# tick-mk-5_0_0.net
KiCad netlist of a schematic drawn in EAGLE
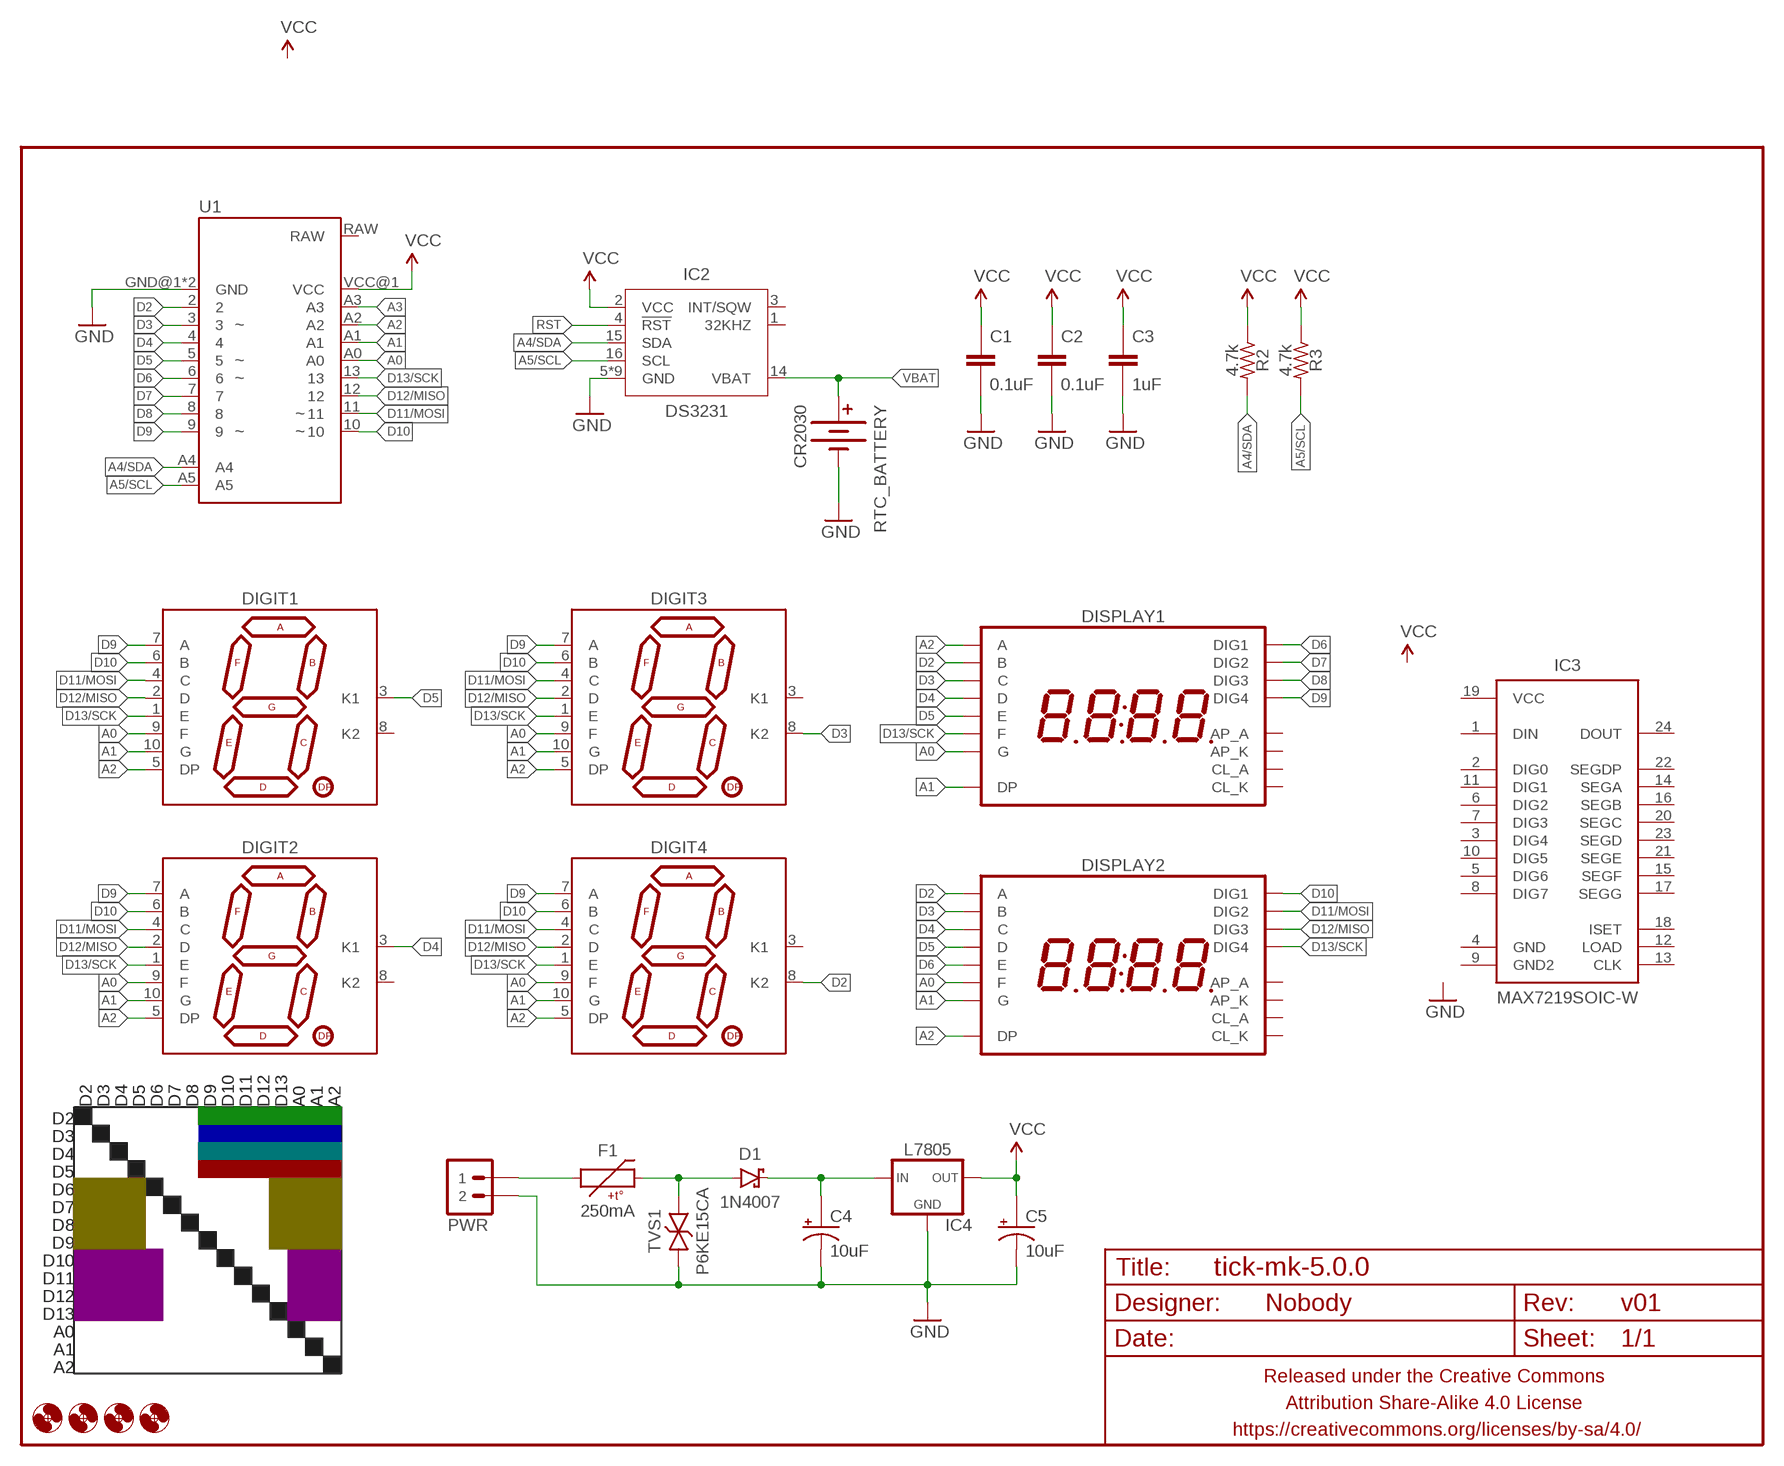
[diagram p0: schematic, sheet 1]

(export (version "E")
  (design (tool "Eeschema 10.0.6"))
  (components
    (comp (ref "C1")
      (value "0.1uF")
      (footprint "eagle-import:C025-024X044")
      (libsource (lib "eagle-import") (part "CAPACITOR-CERAMIC025-024X044"))
    )
    (comp (ref "C2")
      (value "0.1uF")
      (footprint "eagle-import:C025-024X044")
      (libsource (lib "eagle-import") (part "CAPACITOR-CERAMIC025-024X044"))
    )
    (comp (ref "C3")
      (value "1uF")
      (footprint "eagle-import:C025-024X044")
      (libsource (lib "eagle-import") (part "CAPACITOR-CERAMIC025-024X044"))
    )
    (comp (ref "C4")
      (value "10uF")
      (footprint "eagle-import:E2-5")
      (libsource (lib "eagle-import") (part "CAPACITOR-POLARIZEDE2-5"))
    )
    (comp (ref "C5")
      (value "10uF")
      (footprint "eagle-import:E2-5")
      (libsource (lib "eagle-import") (part "CAPACITOR-POLARIZEDE2-5"))
    )
    (comp (ref "D1")
      (value "1N4007")
      (footprint "eagle-import:DIODE-10.16MM")
      (libsource (lib "eagle-import") (part "DIODE-SCHOTTKYPTH-10.16MM"))
    )
    (comp (ref "DIGIT1")
      (value "7SEG_1DIGPTH-25.4MM-BARE")
      (footprint "eagle-import:7SEG_1DIG_25.4MM_NOSILK")
      (libsource (lib "eagle-import") (part "7SEG_1DIGPTH-25.4MM-BARE"))
    )
    (comp (ref "DIGIT2")
      (value "7SEG_1DIGPTH-25.4MM-BARE")
      (footprint "eagle-import:7SEG_1DIG_25.4MM_NOSILK")
      (libsource (lib "eagle-import") (part "7SEG_1DIGPTH-25.4MM-BARE"))
    )
    (comp (ref "DIGIT3")
      (value "7SEG_1DIGPTH-25.4MM-BARE")
      (footprint "eagle-import:7SEG_1DIG_25.4MM_NOSILK")
      (libsource (lib "eagle-import") (part "7SEG_1DIGPTH-25.4MM-BARE"))
    )
    (comp (ref "DIGIT4")
      (value "7SEG_1DIGPTH-25.4MM-BARE")
      (footprint "eagle-import:7SEG_1DIG_25.4MM_NOSILK")
      (libsource (lib "eagle-import") (part "7SEG_1DIGPTH-25.4MM-BARE"))
    )
    (comp (ref "DISPLAY1")
      (value "7SEG_4DIGIT_COLON_APOS")
      (footprint "eagle-import:7SEG_4DIG_10MM")
      (libsource (lib "eagle-import") (part "7SEG_4DIGIT_COLON_APOS"))
    )
    (comp (ref "DISPLAY2")
      (value "7SEG_4DIGIT_COLON_APOS")
      (footprint "eagle-import:7SEG_4DIG_10MM")
      (libsource (lib "eagle-import") (part "7SEG_4DIGIT_COLON_APOS"))
    )
    (comp (ref "F1")
      (value "250mA")
      (footprint "eagle-import:PTC-PTH-5.08MM")
      (libsource (lib "eagle-import") (part "PTCPTH-5.08MM"))
    )
    (comp (ref "FRAME1")
      (value "FRAME-LETTERNO_PACKAGE")
      (footprint "eagle-import:DUMMY")
      (fields (field (name "DESIGNER") "Nobody"))
      (libsource (lib "eagle-import") (part "FRAME-LETTERNO_PACKAGE"))
    )
    (comp (ref "H1")
      (value "HOLE2,5")
      (footprint "eagle-import:2,5")
      (libsource (lib "eagle-import") (part "HOLE2,5"))
    )
    (comp (ref "H2")
      (value "HOLE2,5")
      (footprint "eagle-import:2,5")
      (libsource (lib "eagle-import") (part "HOLE2,5"))
    )
    (comp (ref "H3")
      (value "HOLE2,5")
      (footprint "eagle-import:2,5")
      (libsource (lib "eagle-import") (part "HOLE2,5"))
    )
    (comp (ref "H4")
      (value "HOLE2,5")
      (footprint "eagle-import:2,5")
      (libsource (lib "eagle-import") (part "HOLE2,5"))
    )
    (comp (ref "IC2")
      (value "DS3231")
      (footprint "eagle-import:SO16W")
      (libsource (lib "eagle-import") (part "DS3231"))
    )
    (comp (ref "IC3")
      (value "MAX7219SOIC-W")
      (footprint "eagle-import:SO24W")
      (libsource (lib "eagle-import") (part "MAX7219SOIC-W"))
    )
    (comp (ref "IC4")
      (value "L7805")
      (footprint "eagle-import:TO220-IGO-THERMPAD")
      (libsource (lib "eagle-import") (part "V_REG_78XXTO-220-THERMPAD"))
    )
    (comp (ref "PWR")
      (value "M02JST-PTH-VERT")
      (footprint "eagle-import:JST-2-PH-VERT-PTH")
      (libsource (lib "eagle-import") (part "M02JST-PTH-VERT"))
    )
    (comp (ref "R2")
      (value "4.7k")
      (footprint "eagle-import:RESISTOR-AXIAL-PTH-6.35MM")
      (libsource (lib "eagle-import") (part "RESISTORPTH-AXIAL-6.35MM"))
    )
    (comp (ref "R3")
      (value "4.7k")
      (footprint "eagle-import:RESISTOR-AXIAL-PTH-6.35MM")
      (libsource (lib "eagle-import") (part "RESISTORPTH-AXIAL-6.35MM"))
    )
    (comp (ref "RTC_BATTERY")
      (value "CR2030")
      (footprint "eagle-import:BATTCON_20MM_MINE_STAHPIT")
      (libsource (lib "eagle-import") (part "BATTERY20MM_SMD_TIGHT"))
    )
    (comp (ref "TVS1")
      (value "P6KE15CA")
      (footprint "eagle-import:DO-41-TVS-BI-10.16MM")
      (libsource (lib "eagle-import") (part "TVSDO-41-10.16MM"))
    )
    (comp (ref "U1")
      (value "ARDUINO_PRO_MINI_TICK2")
      (footprint "eagle-import:ARDUINO_PRO_MINI_TICK2")
      (libsource (lib "eagle-import") (part "ARDUINO_PRO_MINI_TICK2"))
    )
  )
  (nets
    (net (code "1") (name "A0") (class "Default")
      (node (ref "DIGIT1") (pin "9") (pinfunction "F_9") (pintype "bidirectional"))
      (node (ref "DIGIT2") (pin "9") (pinfunction "F_9") (pintype "bidirectional"))
      (node (ref "DIGIT3") (pin "9") (pinfunction "F_9") (pintype "bidirectional"))
      (node (ref "DIGIT4") (pin "9") (pinfunction "F_9") (pintype "bidirectional"))
      (node (ref "DISPLAY1") (pin "15") (pinfunction "G_15") (pintype "passive"))
      (node (ref "DISPLAY2") (pin "11") (pinfunction "F_11") (pintype "passive"))
      (node (ref "U1") (pin "A0") (pinfunction "A0_A0") (pintype "bidirectional"))
    )
    (net (code "2") (name "A1") (class "Default")
      (node (ref "DIGIT1") (pin "10") (pinfunction "G_10") (pintype "bidirectional"))
      (node (ref "DIGIT2") (pin "10") (pinfunction "G_10") (pintype "bidirectional"))
      (node (ref "DIGIT3") (pin "10") (pinfunction "G_10") (pintype "bidirectional"))
      (node (ref "DIGIT4") (pin "10") (pinfunction "G_10") (pintype "bidirectional"))
      (node (ref "DISPLAY1") (pin "7") (pinfunction "DP_7") (pintype "passive"))
      (node (ref "DISPLAY2") (pin "15") (pinfunction "G_15") (pintype "passive"))
      (node (ref "U1") (pin "A1") (pinfunction "A1_A1") (pintype "bidirectional"))
    )
    (net (code "3") (name "A2") (class "Default")
      (node (ref "DIGIT1") (pin "5") (pinfunction "DP_5") (pintype "bidirectional"))
      (node (ref "DIGIT2") (pin "5") (pinfunction "DP_5") (pintype "bidirectional"))
      (node (ref "DIGIT3") (pin "5") (pinfunction "DP_5") (pintype "bidirectional"))
      (node (ref "DIGIT4") (pin "5") (pinfunction "DP_5") (pintype "bidirectional"))
      (node (ref "DISPLAY1") (pin "14") (pinfunction "A_14") (pintype "passive"))
      (node (ref "DISPLAY2") (pin "7") (pinfunction "DP_7") (pintype "passive"))
      (node (ref "U1") (pin "A2") (pinfunction "A2_A2") (pintype "bidirectional"))
    )
    (net (code "4") (name "A3") (class "Default")
      (node (ref "U1") (pin "A3") (pinfunction "A3_A3") (pintype "bidirectional"))
    )
    (net (code "5") (name "A4{slash}SDA") (class "Default")
      (node (ref "IC2") (pin "15") (pinfunction "SDA_15") (pintype "bidirectional"))
      (node (ref "R2") (pin "P$2") (pinfunction "2_P$2") (pintype "passive"))
      (node (ref "U1") (pin "A4") (pinfunction "A4_A4") (pintype "bidirectional"))
    )
    (net (code "6") (name "A5{slash}SCL") (class "Default")
      (node (ref "IC2") (pin "16") (pinfunction "SCL_16") (pintype "bidirectional"))
      (node (ref "R3") (pin "P$2") (pinfunction "2_P$2") (pintype "passive"))
      (node (ref "U1") (pin "A5") (pinfunction "A5_A5") (pintype "bidirectional"))
    )
    (net (code "7") (name "D2") (class "Default")
      (node (ref "DIGIT4") (pin "8") (pinfunction "K2_8") (pintype "bidirectional"))
      (node (ref "DISPLAY1") (pin "16") (pinfunction "B_16") (pintype "passive"))
      (node (ref "DISPLAY2") (pin "14") (pinfunction "A_14") (pintype "passive"))
      (node (ref "U1") (pin "2") (pinfunction "2_2") (pintype "bidirectional"))
    )
    (net (code "8") (name "D3") (class "Default")
      (node (ref "DIGIT3") (pin "8") (pinfunction "K2_8") (pintype "bidirectional"))
      (node (ref "DISPLAY1") (pin "13") (pinfunction "C_13") (pintype "passive"))
      (node (ref "DISPLAY2") (pin "16") (pinfunction "B_16") (pintype "passive"))
      (node (ref "U1") (pin "3") (pinfunction "3_3") (pintype "bidirectional"))
    )
    (net (code "9") (name "D4") (class "Default")
      (node (ref "DIGIT2") (pin "3") (pinfunction "K1_3") (pintype "bidirectional"))
      (node (ref "DISPLAY1") (pin "3") (pinfunction "D_3") (pintype "passive"))
      (node (ref "DISPLAY2") (pin "13") (pinfunction "C_13") (pintype "passive"))
      (node (ref "U1") (pin "4") (pinfunction "4_4") (pintype "bidirectional"))
    )
    (net (code "10") (name "D5") (class "Default")
      (node (ref "DIGIT1") (pin "3") (pinfunction "K1_3") (pintype "bidirectional"))
      (node (ref "DISPLAY1") (pin "5") (pinfunction "E_5") (pintype "passive"))
      (node (ref "DISPLAY2") (pin "3") (pinfunction "D_3") (pintype "passive"))
      (node (ref "U1") (pin "5") (pinfunction "5_5") (pintype "bidirectional"))
    )
    (net (code "11") (name "D6") (class "Default")
      (node (ref "DISPLAY1") (pin "1") (pinfunction "DIG1_1") (pintype "passive"))
      (node (ref "DISPLAY2") (pin "5") (pinfunction "E_5") (pintype "passive"))
      (node (ref "U1") (pin "6") (pinfunction "6_6") (pintype "bidirectional"))
    )
    (net (code "12") (name "D7") (class "Default")
      (node (ref "DISPLAY1") (pin "2") (pinfunction "DIG2_2") (pintype "passive"))
      (node (ref "U1") (pin "7") (pinfunction "7_7") (pintype "bidirectional"))
    )
    (net (code "13") (name "D8") (class "Default")
      (node (ref "DISPLAY1") (pin "6") (pinfunction "DIG3_6") (pintype "passive"))
      (node (ref "U1") (pin "8") (pinfunction "8_8") (pintype "bidirectional"))
    )
    (net (code "14") (name "D9") (class "Default")
      (node (ref "DIGIT1") (pin "7") (pinfunction "A_7") (pintype "bidirectional"))
      (node (ref "DIGIT2") (pin "7") (pinfunction "A_7") (pintype "bidirectional"))
      (node (ref "DIGIT3") (pin "7") (pinfunction "A_7") (pintype "bidirectional"))
      (node (ref "DIGIT4") (pin "7") (pinfunction "A_7") (pintype "bidirectional"))
      (node (ref "DISPLAY1") (pin "8") (pinfunction "DIG4_8") (pintype "passive"))
      (node (ref "U1") (pin "9") (pinfunction "9_9") (pintype "bidirectional"))
    )
    (net (code "15") (name "D10") (class "Default")
      (node (ref "DIGIT1") (pin "6") (pinfunction "B_6") (pintype "bidirectional"))
      (node (ref "DIGIT2") (pin "6") (pinfunction "B_6") (pintype "bidirectional"))
      (node (ref "DIGIT3") (pin "6") (pinfunction "B_6") (pintype "bidirectional"))
      (node (ref "DIGIT4") (pin "6") (pinfunction "B_6") (pintype "bidirectional"))
      (node (ref "DISPLAY2") (pin "1") (pinfunction "DIG1_1") (pintype "passive"))
      (node (ref "U1") (pin "10") (pinfunction "10_10") (pintype "bidirectional"))
    )
    (net (code "16") (name "D11{slash}MOSI") (class "Default")
      (node (ref "DIGIT1") (pin "4") (pinfunction "C_4") (pintype "bidirectional"))
      (node (ref "DIGIT2") (pin "4") (pinfunction "C_4") (pintype "bidirectional"))
      (node (ref "DIGIT3") (pin "4") (pinfunction "C_4") (pintype "bidirectional"))
      (node (ref "DIGIT4") (pin "4") (pinfunction "C_4") (pintype "bidirectional"))
      (node (ref "DISPLAY2") (pin "2") (pinfunction "DIG2_2") (pintype "passive"))
      (node (ref "U1") (pin "11") (pinfunction "11_11") (pintype "bidirectional"))
    )
    (net (code "17") (name "D12{slash}MISO") (class "Default")
      (node (ref "DIGIT1") (pin "2") (pinfunction "D_2") (pintype "bidirectional"))
      (node (ref "DIGIT2") (pin "2") (pinfunction "D_2") (pintype "bidirectional"))
      (node (ref "DIGIT3") (pin "2") (pinfunction "D_2") (pintype "bidirectional"))
      (node (ref "DIGIT4") (pin "2") (pinfunction "D_2") (pintype "bidirectional"))
      (node (ref "DISPLAY2") (pin "6") (pinfunction "DIG3_6") (pintype "passive"))
      (node (ref "U1") (pin "12") (pinfunction "12_12") (pintype "bidirectional"))
    )
    (net (code "18") (name "D13{slash}SCK") (class "Default")
      (node (ref "DIGIT1") (pin "1") (pinfunction "E_1") (pintype "bidirectional"))
      (node (ref "DIGIT2") (pin "1") (pinfunction "E_1") (pintype "bidirectional"))
      (node (ref "DIGIT3") (pin "1") (pinfunction "E_1") (pintype "bidirectional"))
      (node (ref "DIGIT4") (pin "1") (pinfunction "E_1") (pintype "bidirectional"))
      (node (ref "DISPLAY1") (pin "11") (pinfunction "F_11") (pintype "passive"))
      (node (ref "DISPLAY2") (pin "8") (pinfunction "DIG4_8") (pintype "passive"))
      (node (ref "U1") (pin "13") (pinfunction "13_13") (pintype "bidirectional"))
    )
    (net (code "19") (name "GND") (class "Default")
      (node (ref "C1") (pin "2") (pinfunction "2_2") (pintype "passive"))
      (node (ref "C2") (pin "2") (pinfunction "2_2") (pintype "passive"))
      (node (ref "C3") (pin "2") (pinfunction "2_2") (pintype "passive"))
      (node (ref "C4") (pin "-") (pinfunction "-_-") (pintype "passive"))
      (node (ref "C5") (pin "-") (pinfunction "-_-") (pintype "passive"))
      (node (ref "IC2") (pin "10") (pinfunction "GND_10") (pintype "bidirectional"))
      (node (ref "IC2") (pin "11") (pinfunction "GND_11") (pintype "bidirectional"))
      (node (ref "IC2") (pin "12") (pinfunction "GND_12") (pintype "bidirectional"))
      (node (ref "IC2") (pin "13") (pinfunction "GND_13") (pintype "bidirectional"))
      (node (ref "IC2") (pin "5") (pinfunction "GND_5") (pintype "bidirectional"))
      (node (ref "IC2") (pin "6") (pinfunction "GND_6") (pintype "bidirectional"))
      (node (ref "IC2") (pin "7") (pinfunction "GND_7") (pintype "bidirectional"))
      (node (ref "IC2") (pin "8") (pinfunction "GND_8") (pintype "bidirectional"))
      (node (ref "IC2") (pin "9") (pinfunction "GND_9") (pintype "bidirectional"))
      (node (ref "IC4") (pin "4") (pinfunction "GND_4") (pintype "bidirectional"))
      (node (ref "IC4") (pin "GND") (pinfunction "GND_GND") (pintype "bidirectional"))
      (node (ref "PWR") (pin "2") (pinfunction "2_2") (pintype "passive"))
      (node (ref "RTC_BATTERY") (pin "BOTTOM") (pinfunction "-_BOTTOM") (pintype "power_in"))
      (node (ref "TVS1") (pin "P$1") (pinfunction "1_P$1") (pintype "passive"))
      (node (ref "U1") (pin "GND@1") (pinfunction "GND_GND@1") (pintype "bidirectional"))
      (node (ref "U1") (pin "GND@2") (pinfunction "GND_GND@2") (pintype "bidirectional"))
    )
    (net (code "20") (name "Net-(C4-Pad+)") (class "Default")
      (node (ref "C4") (pin "+") (pinfunction "+_+") (pintype "passive"))
      (node (ref "D1") (pin "C") (pinfunction "C_C") (pintype "passive"))
      (node (ref "IC4") (pin "IN") (pinfunction "IN_IN") (pintype "bidirectional"))
    )
    (net (code "21") (name "Net-(F1-1)") (class "Default")
      (node (ref "F1") (pin "P$1") (pinfunction "1_P$1") (pintype "passive"))
      (node (ref "PWR") (pin "1") (pinfunction "1_1") (pintype "passive"))
    )
    (net (code "22") (name "Net-(F1-2)") (class "Default")
      (node (ref "D1") (pin "A") (pinfunction "A_A") (pintype "passive"))
      (node (ref "F1") (pin "P$2") (pinfunction "2_P$2") (pintype "passive"))
      (node (ref "TVS1") (pin "P$2") (pinfunction "2_P$2") (pintype "passive"))
    )
    (net (code "23") (name "RST") (class "Default")
      (node (ref "IC2") (pin "4") (pinfunction "~{RST}_4") (pintype "bidirectional"))
    )
    (net (code "24") (name "VBAT") (class "Default")
      (node (ref "IC2") (pin "14") (pinfunction "VBAT_14") (pintype "bidirectional"))
      (node (ref "RTC_BATTERY") (pin "TOP@1") (pinfunction "+_TOP@1") (pintype "power_in"))
      (node (ref "RTC_BATTERY") (pin "TOP@2") (pinfunction "+_TOP@2") (pintype "power_in"))
    )
    (net (code "25") (name "VCC") (class "Default")
      (node (ref "C1") (pin "1") (pinfunction "1_1") (pintype "passive"))
      (node (ref "C2") (pin "1") (pinfunction "1_1") (pintype "passive"))
      (node (ref "C3") (pin "1") (pinfunction "1_1") (pintype "passive"))
      (node (ref "C5") (pin "+") (pinfunction "+_+") (pintype "passive"))
      (node (ref "IC2") (pin "2") (pinfunction "VCC_2") (pintype "bidirectional"))
      (node (ref "IC4") (pin "OUT") (pinfunction "OUT_OUT") (pintype "bidirectional"))
      (node (ref "R2") (pin "P$1") (pinfunction "1_P$1") (pintype "passive"))
      (node (ref "R3") (pin "P$1") (pinfunction "1_P$1") (pintype "passive"))
      (node (ref "U1") (pin "VCC@1") (pinfunction "VCC_VCC@1") (pintype "bidirectional"))
    )
    (net (code "26") (name "unconnected-(DIGIT1-K2-Pad8)") (class "Default")
      (node (ref "DIGIT1") (pin "8") (pinfunction "K2_8") (pintype "bidirectional"))
    )
    (net (code "27") (name "unconnected-(DIGIT2-K2-Pad8)") (class "Default")
      (node (ref "DIGIT2") (pin "8") (pinfunction "K2_8") (pintype "bidirectional"))
    )
    (net (code "28") (name "unconnected-(DIGIT3-K1-Pad3)") (class "Default")
      (node (ref "DIGIT3") (pin "3") (pinfunction "K1_3") (pintype "bidirectional"))
    )
    (net (code "29") (name "unconnected-(DIGIT4-K1-Pad3)") (class "Default")
      (node (ref "DIGIT4") (pin "3") (pinfunction "K1_3") (pintype "bidirectional"))
    )
    (net (code "30") (name "unconnected-(DISPLAY1-AP_A-Pad10)") (class "Default")
      (node (ref "DISPLAY1") (pin "10") (pinfunction "AP_A_10") (pintype "bidirectional"))
    )
    (net (code "31") (name "unconnected-(DISPLAY1-AP_K-Pad9)") (class "Default")
      (node (ref "DISPLAY1") (pin "9") (pinfunction "AP_K_9") (pintype "bidirectional"))
    )
    (net (code "32") (name "unconnected-(DISPLAY1-CL_A-Pad4)") (class "Default")
      (node (ref "DISPLAY1") (pin "4") (pinfunction "CL_A_4") (pintype "passive"))
    )
    (net (code "33") (name "unconnected-(DISPLAY1-CL_K-Pad12)") (class "Default")
      (node (ref "DISPLAY1") (pin "12") (pinfunction "CL_K_12") (pintype "passive"))
    )
    (net (code "34") (name "unconnected-(DISPLAY2-AP_A-Pad10)") (class "Default")
      (node (ref "DISPLAY2") (pin "10") (pinfunction "AP_A_10") (pintype "bidirectional"))
    )
    (net (code "35") (name "unconnected-(DISPLAY2-AP_K-Pad9)") (class "Default")
      (node (ref "DISPLAY2") (pin "9") (pinfunction "AP_K_9") (pintype "bidirectional"))
    )
    (net (code "36") (name "unconnected-(DISPLAY2-CL_A-Pad4)") (class "Default")
      (node (ref "DISPLAY2") (pin "4") (pinfunction "CL_A_4") (pintype "passive"))
    )
    (net (code "37") (name "unconnected-(DISPLAY2-CL_K-Pad12)") (class "Default")
      (node (ref "DISPLAY2") (pin "12") (pinfunction "CL_K_12") (pintype "passive"))
    )
    (net (code "38") (name "unconnected-(IC2-32KHZ-Pad1)") (class "Default")
      (node (ref "IC2") (pin "1") (pinfunction "32KHZ_1") (pintype "bidirectional"))
    )
    (net (code "39") (name "unconnected-(IC2-INT{slash}SQW-Pad3)") (class "Default")
      (node (ref "IC2") (pin "3") (pinfunction "INT/SQW_3") (pintype "bidirectional"))
    )
    (net (code "40") (name "unconnected-(IC3-CLK-Pad13)") (class "Default")
      (node (ref "IC3") (pin "13") (pinfunction "CLK_13") (pintype "bidirectional"))
    )
    (net (code "41") (name "unconnected-(IC3-DIG0-Pad2)") (class "Default")
      (node (ref "IC3") (pin "2") (pinfunction "DIG0_2") (pintype "bidirectional"))
    )
    (net (code "42") (name "unconnected-(IC3-DIG1-Pad11)") (class "Default")
      (node (ref "IC3") (pin "11") (pinfunction "DIG1_11") (pintype "bidirectional"))
    )
    (net (code "43") (name "unconnected-(IC3-DIG2-Pad6)") (class "Default")
      (node (ref "IC3") (pin "6") (pinfunction "DIG2_6") (pintype "bidirectional"))
    )
    (net (code "44") (name "unconnected-(IC3-DIG3-Pad7)") (class "Default")
      (node (ref "IC3") (pin "7") (pinfunction "DIG3_7") (pintype "bidirectional"))
    )
    (net (code "45") (name "unconnected-(IC3-DIG4-Pad3)") (class "Default")
      (node (ref "IC3") (pin "3") (pinfunction "DIG4_3") (pintype "bidirectional"))
    )
    (net (code "46") (name "unconnected-(IC3-DIG5-Pad10)") (class "Default")
      (node (ref "IC3") (pin "10") (pinfunction "DIG5_10") (pintype "bidirectional"))
    )
    (net (code "47") (name "unconnected-(IC3-DIG6-Pad5)") (class "Default")
      (node (ref "IC3") (pin "5") (pinfunction "DIG6_5") (pintype "bidirectional"))
    )
    (net (code "48") (name "unconnected-(IC3-DIG7-Pad8)") (class "Default")
      (node (ref "IC3") (pin "8") (pinfunction "DIG7_8") (pintype "bidirectional"))
    )
    (net (code "49") (name "unconnected-(IC3-DIN-Pad1)") (class "Default")
      (node (ref "IC3") (pin "1") (pinfunction "DIN_1") (pintype "bidirectional"))
    )
    (net (code "50") (name "unconnected-(IC3-DOUT-Pad24)") (class "Default")
      (node (ref "IC3") (pin "24") (pinfunction "DOUT_24") (pintype "bidirectional"))
    )
    (net (code "51") (name "unconnected-(IC3-GND-Pad4)") (class "Default")
      (node (ref "IC3") (pin "4") (pinfunction "GND_4") (pintype "bidirectional"))
    )
    (net (code "52") (name "unconnected-(IC3-GND2-Pad9)") (class "Default")
      (node (ref "IC3") (pin "9") (pinfunction "GND2_9") (pintype "bidirectional"))
    )
    (net (code "53") (name "unconnected-(IC3-ISET-Pad18)") (class "Default")
      (node (ref "IC3") (pin "18") (pinfunction "ISET_18") (pintype "bidirectional"))
    )
    (net (code "54") (name "unconnected-(IC3-LOAD-Pad12)") (class "Default")
      (node (ref "IC3") (pin "12") (pinfunction "LOAD_12") (pintype "bidirectional"))
    )
    (net (code "55") (name "unconnected-(IC3-SEGA-Pad14)") (class "Default")
      (node (ref "IC3") (pin "14") (pinfunction "SEGA_14") (pintype "bidirectional"))
    )
    (net (code "56") (name "unconnected-(IC3-SEGB-Pad16)") (class "Default")
      (node (ref "IC3") (pin "16") (pinfunction "SEGB_16") (pintype "bidirectional"))
    )
    (net (code "57") (name "unconnected-(IC3-SEGC-Pad20)") (class "Default")
      (node (ref "IC3") (pin "20") (pinfunction "SEGC_20") (pintype "bidirectional"))
    )
    (net (code "58") (name "unconnected-(IC3-SEGD-Pad23)") (class "Default")
      (node (ref "IC3") (pin "23") (pinfunction "SEGD_23") (pintype "bidirectional"))
    )
    (net (code "59") (name "unconnected-(IC3-SEGDP-Pad22)") (class "Default")
      (node (ref "IC3") (pin "22") (pinfunction "SEGDP_22") (pintype "bidirectional"))
    )
    (net (code "60") (name "unconnected-(IC3-SEGE-Pad21)") (class "Default")
      (node (ref "IC3") (pin "21") (pinfunction "SEGE_21") (pintype "bidirectional"))
    )
    (net (code "61") (name "unconnected-(IC3-SEGF-Pad15)") (class "Default")
      (node (ref "IC3") (pin "15") (pinfunction "SEGF_15") (pintype "bidirectional"))
    )
    (net (code "62") (name "unconnected-(IC3-SEGG-Pad17)") (class "Default")
      (node (ref "IC3") (pin "17") (pinfunction "SEGG_17") (pintype "bidirectional"))
    )
    (net (code "63") (name "unconnected-(IC3-VCC-Pad19)") (class "Default")
      (node (ref "IC3") (pin "19") (pinfunction "VCC_19") (pintype "bidirectional"))
    )
    (net (code "64") (name "unconnected-(U1-PadRAW)") (class "Default")
      (node (ref "U1") (pin "RAW") (pinfunction "RAW_RAW") (pintype "bidirectional"))
    )
  )
)
